# akabeacon_square_da14580_small.net
KiCad netlist of a schematic drawn in EAGLE
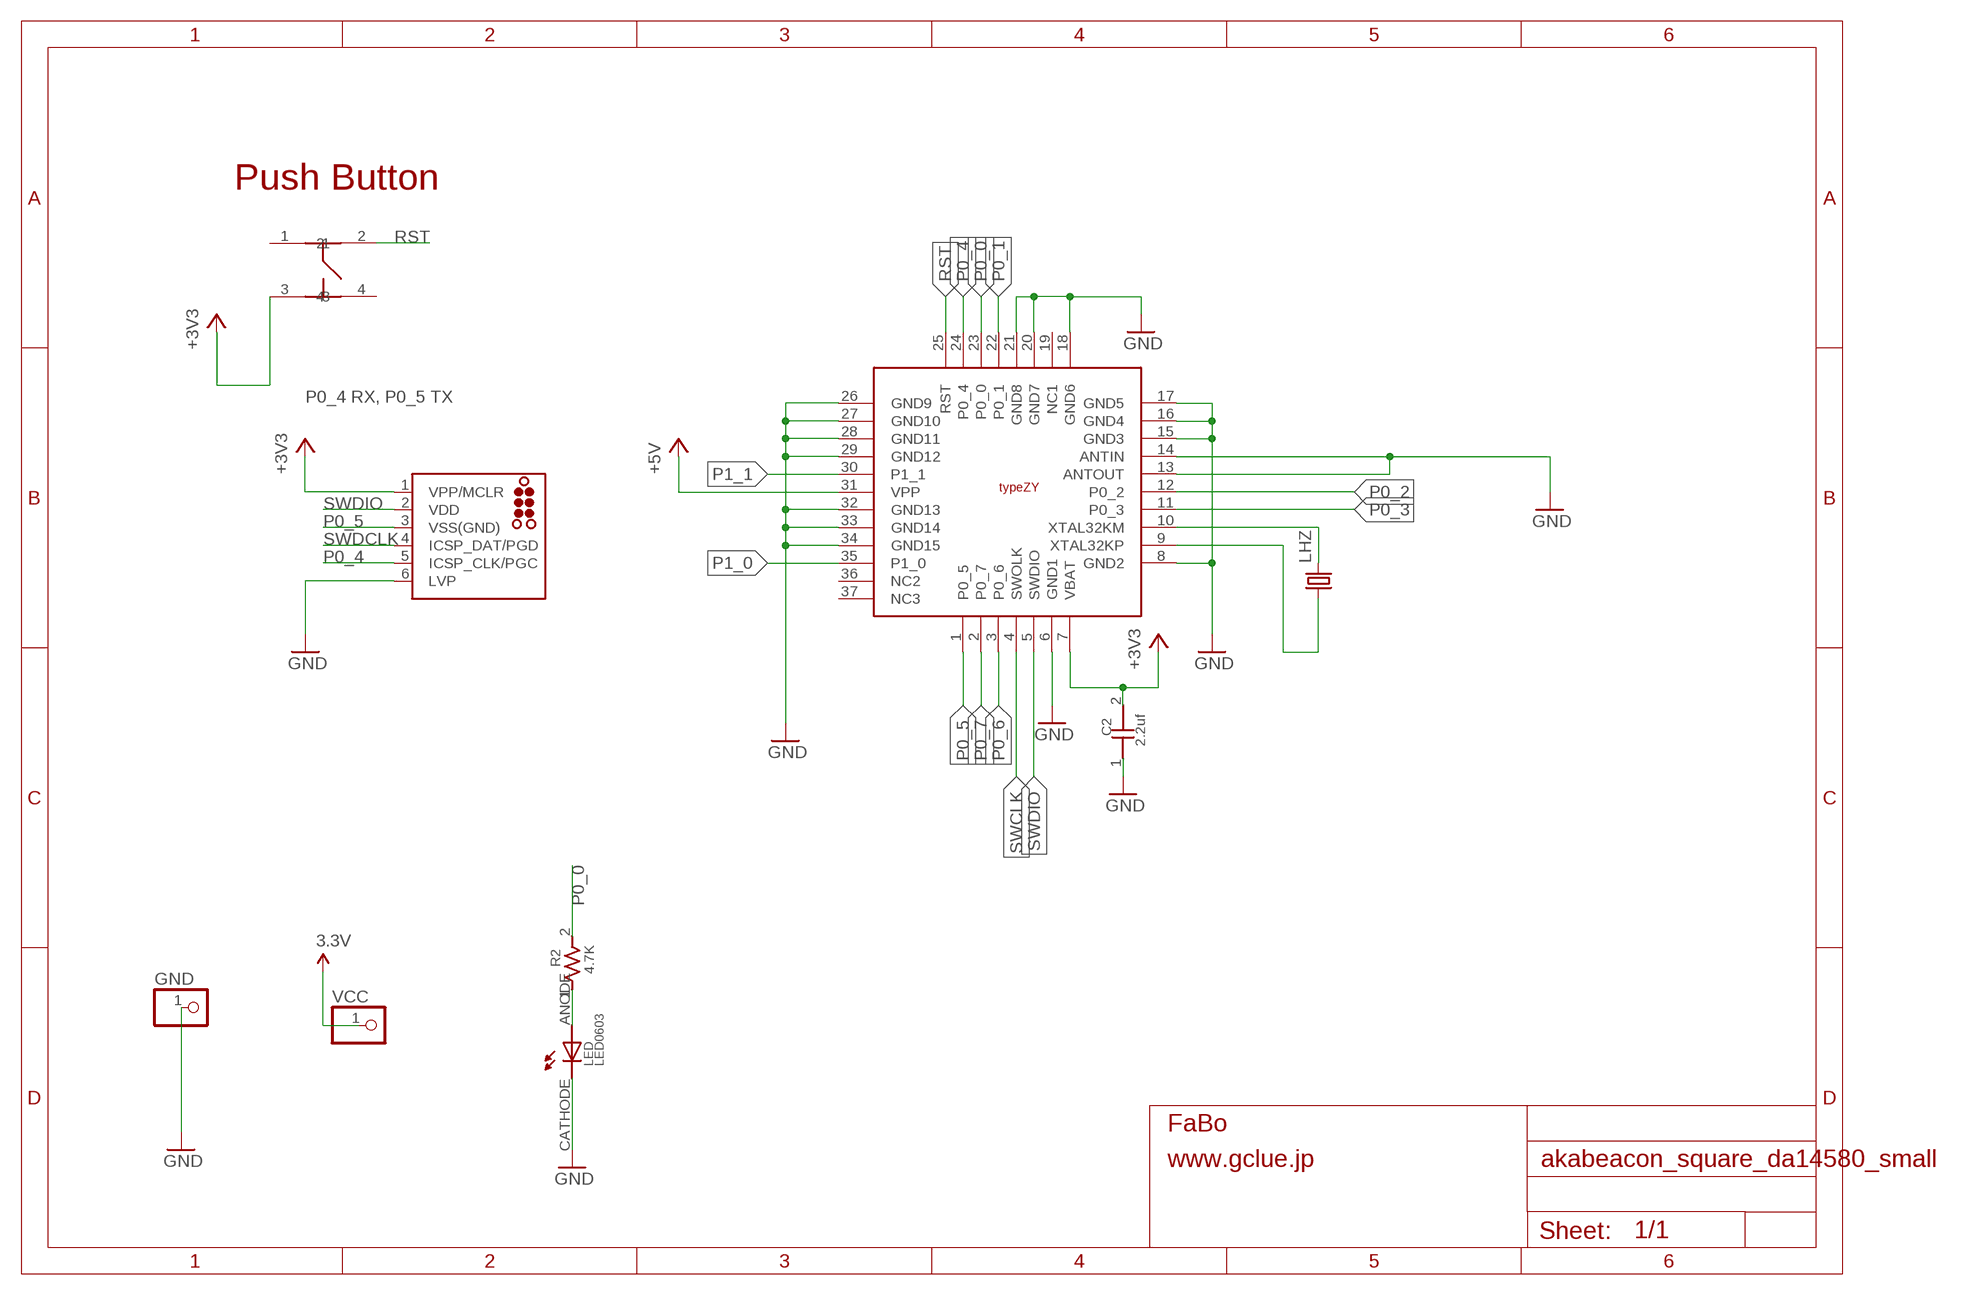
[diagram p0: schematic, sheet 1]

(export (version "E")
  (design (tool "Eeschema 10.0.6"))
  (components
    (comp (ref "C2")
      (value "2.2uf")
      (footprint "eagle-import:0603")
      (libsource (lib "eagle-import") (part "CAPACITOR0603"))
    )
    (comp (ref "GND")
      (value "PINHD-1X1CB")
      (footprint "eagle-import:1X01-CLEANBIG")
      (libsource (lib "eagle-import") (part "PINHD-1X1CB"))
    )
    (comp (ref "J2")
      (value "TC2030-MCP")
      (footprint "eagle-import:TC2030-MCP")
      (libsource (lib "eagle-import") (part "TC2030-MCP"))
    )
    (comp (ref "LED")
      (value "LED0603")
      (footprint "eagle-import:0603")
      (libsource (lib "eagle-import") (part "LED0603"))
    )
    (comp (ref "LHZ")
      (value "FC-12M")
      (footprint "eagle-import:FC-12M")
      (libsource (lib "eagle-import") (part "FC-12M"))
    )
    (comp (ref "R2")
      (value "4.7K")
      (footprint "eagle-import:0603")
      (libsource (lib "eagle-import") (part "RESISTOR0603"))
    )
    (comp (ref "U$7")
      (value "SWICTH-4P(KMR2)")
      (footprint "eagle-import:SWITCH-4P(KMR2)")
      (libsource (lib "eagle-import") (part "SWICTH-4P(KMR2)"))
    )
    (comp (ref "U$9")
      (value "MURATA-TYPEZY")
      (footprint "eagle-import:MURATA_TYPEZY")
      (libsource (lib "eagle-import") (part "MURATA-TYPEZY"))
    )
    (comp (ref "VCC")
      (value "PINHD-1X1CB")
      (footprint "eagle-import:1X01-CLEANBIG")
      (libsource (lib "eagle-import") (part "PINHD-1X1CB"))
    )
  )
  (nets
    (net (code "1") (name "+3V3") (class "Default")
      (node (ref "C2") (pin "2") (pinfunction "2_2") (pintype "passive"))
      (node (ref "J2") (pin "1") (pinfunction "VPP/MCLR_1") (pintype "passive"))
      (node (ref "U$7") (pin "3") (pinfunction "3_3") (pintype "bidirectional"))
      (node (ref "U$9") (pin "7") (pinfunction "VBAT_7") (pintype "bidirectional"))
    )
    (net (code "2") (name "+5V") (class "Default")
      (node (ref "U$9") (pin "31") (pinfunction "VPP_31") (pintype "bidirectional"))
    )
    (net (code "3") (name "/SWDCLK") (class "Default")
      (node (ref "J2") (pin "4") (pinfunction "ICSP_DAT/PGD_4") (pintype "bidirectional"))
    )
    (net (code "4") (name "3.3V") (class "Default")
      (node (ref "VCC") (pin "1") (pinfunction "1_1") (pintype "passive"))
    )
    (net (code "5") (name "GND") (class "Default")
      (node (ref "C2") (pin "1") (pinfunction "1_1") (pintype "passive"))
      (node (ref "GND") (pin "1") (pinfunction "1_1") (pintype "passive"))
      (node (ref "J2") (pin "6") (pinfunction "LVP_6") (pintype "bidirectional"))
      (node (ref "LED") (pin "CATHODE") (pinfunction "CATHODE_CATHODE") (pintype "passive"))
      (node (ref "U$9") (pin "13") (pinfunction "ANTOUT_13") (pintype "bidirectional"))
      (node (ref "U$9") (pin "14") (pinfunction "ANTIN_14") (pintype "bidirectional"))
      (node (ref "U$9") (pin "15") (pinfunction "GND3_15") (pintype "bidirectional"))
      (node (ref "U$9") (pin "16") (pinfunction "GND4_16") (pintype "bidirectional"))
      (node (ref "U$9") (pin "17") (pinfunction "GND5_17") (pintype "bidirectional"))
      (node (ref "U$9") (pin "18") (pinfunction "GND6_18") (pintype "bidirectional"))
      (node (ref "U$9") (pin "20") (pinfunction "GND7_20") (pintype "bidirectional"))
      (node (ref "U$9") (pin "21") (pinfunction "GND8_21") (pintype "bidirectional"))
      (node (ref "U$9") (pin "26") (pinfunction "GND9_26") (pintype "bidirectional"))
      (node (ref "U$9") (pin "27") (pinfunction "GND10_27") (pintype "bidirectional"))
      (node (ref "U$9") (pin "28") (pinfunction "GND11_28") (pintype "bidirectional"))
      (node (ref "U$9") (pin "29") (pinfunction "GND12_29") (pintype "bidirectional"))
      (node (ref "U$9") (pin "32") (pinfunction "GND13_32") (pintype "bidirectional"))
      (node (ref "U$9") (pin "33") (pinfunction "GND14_33") (pintype "bidirectional"))
      (node (ref "U$9") (pin "34") (pinfunction "GND15_34") (pintype "bidirectional"))
      (node (ref "U$9") (pin "6") (pinfunction "GND1_6") (pintype "bidirectional"))
      (node (ref "U$9") (pin "8") (pinfunction "GND2_8") (pintype "bidirectional"))
    )
    (net (code "6") (name "Net-(LED-PadANODE)") (class "Default")
      (node (ref "LED") (pin "ANODE") (pinfunction "ANODE_ANODE") (pintype "passive"))
      (node (ref "R2") (pin "1") (pinfunction "1_1") (pintype "passive"))
    )
    (net (code "7") (name "Net-(U$9-XTAL32KM)") (class "Default")
      (node (ref "LHZ") (pin "2") (pinfunction "2_2") (pintype "passive"))
      (node (ref "U$9") (pin "10") (pinfunction "XTAL32KM_10") (pintype "bidirectional"))
    )
    (net (code "8") (name "Net-(U$9-XTAL32KP)") (class "Default")
      (node (ref "LHZ") (pin "1") (pinfunction "1_1") (pintype "passive"))
      (node (ref "U$9") (pin "9") (pinfunction "XTAL32KP_9") (pintype "bidirectional"))
    )
    (net (code "9") (name "P0_0") (class "Default")
      (node (ref "R2") (pin "2") (pinfunction "2_2") (pintype "passive"))
      (node (ref "U$9") (pin "23") (pinfunction "P0_0_23") (pintype "bidirectional"))
    )
    (net (code "10") (name "P0_1") (class "Default")
      (node (ref "U$9") (pin "22") (pinfunction "P0_1_22") (pintype "bidirectional"))
    )
    (net (code "11") (name "P0_2") (class "Default")
      (node (ref "U$9") (pin "12") (pinfunction "P0_2_12") (pintype "bidirectional"))
    )
    (net (code "12") (name "P0_3") (class "Default")
      (node (ref "U$9") (pin "11") (pinfunction "P0_3_11") (pintype "bidirectional"))
    )
    (net (code "13") (name "P0_4") (class "Default")
      (node (ref "J2") (pin "5") (pinfunction "ICSP_CLK/PGC_5") (pintype "output"))
      (node (ref "U$9") (pin "24") (pinfunction "P0_4_24") (pintype "bidirectional"))
    )
    (net (code "14") (name "P0_5") (class "Default")
      (node (ref "J2") (pin "3") (pinfunction "VSS(GND)_3") (pintype "power_in"))
      (node (ref "U$9") (pin "1") (pinfunction "P0_5_1") (pintype "bidirectional"))
    )
    (net (code "15") (name "P0_6") (class "Default")
      (node (ref "U$9") (pin "3") (pinfunction "P0_6_3") (pintype "bidirectional"))
    )
    (net (code "16") (name "P0_7") (class "Default")
      (node (ref "U$9") (pin "2") (pinfunction "P0_7_2") (pintype "bidirectional"))
    )
    (net (code "17") (name "P1_0") (class "Default")
      (node (ref "U$9") (pin "35") (pinfunction "P1_0_35") (pintype "bidirectional"))
    )
    (net (code "18") (name "P1_1") (class "Default")
      (node (ref "U$9") (pin "30") (pinfunction "P1_1_30") (pintype "bidirectional"))
    )
    (net (code "19") (name "RST") (class "Default")
      (node (ref "U$7") (pin "2") (pinfunction "2_2") (pintype "bidirectional"))
      (node (ref "U$9") (pin "25") (pinfunction "RST_25") (pintype "bidirectional"))
    )
    (net (code "20") (name "SWCLK") (class "Default")
      (node (ref "U$9") (pin "4") (pinfunction "SWOLK_4") (pintype "bidirectional"))
    )
    (net (code "21") (name "SWDIO") (class "Default")
      (node (ref "J2") (pin "2") (pinfunction "VDD_2") (pintype "power_in"))
      (node (ref "U$9") (pin "5") (pinfunction "SWDIO_5") (pintype "bidirectional"))
    )
    (net (code "22") (name "unconnected-(U$7-Pad1)") (class "Default")
      (node (ref "U$7") (pin "1") (pinfunction "1_1") (pintype "bidirectional"))
    )
    (net (code "23") (name "unconnected-(U$7-Pad4)") (class "Default")
      (node (ref "U$7") (pin "4") (pinfunction "4_4") (pintype "bidirectional"))
    )
    (net (code "24") (name "unconnected-(U$9-NC1-Pad19)") (class "Default")
      (node (ref "U$9") (pin "19") (pinfunction "NC1_19") (pintype "bidirectional"))
    )
    (net (code "25") (name "unconnected-(U$9-NC2-Pad36)") (class "Default")
      (node (ref "U$9") (pin "36") (pinfunction "NC2_36") (pintype "bidirectional"))
    )
    (net (code "26") (name "unconnected-(U$9-NC3-Pad37)") (class "Default")
      (node (ref "U$9") (pin "37") (pinfunction "NC3_37") (pintype "bidirectional"))
    )
  )
)
